# eeZeePowerJack.net
KiCad netlist of a schematic drawn in EAGLE
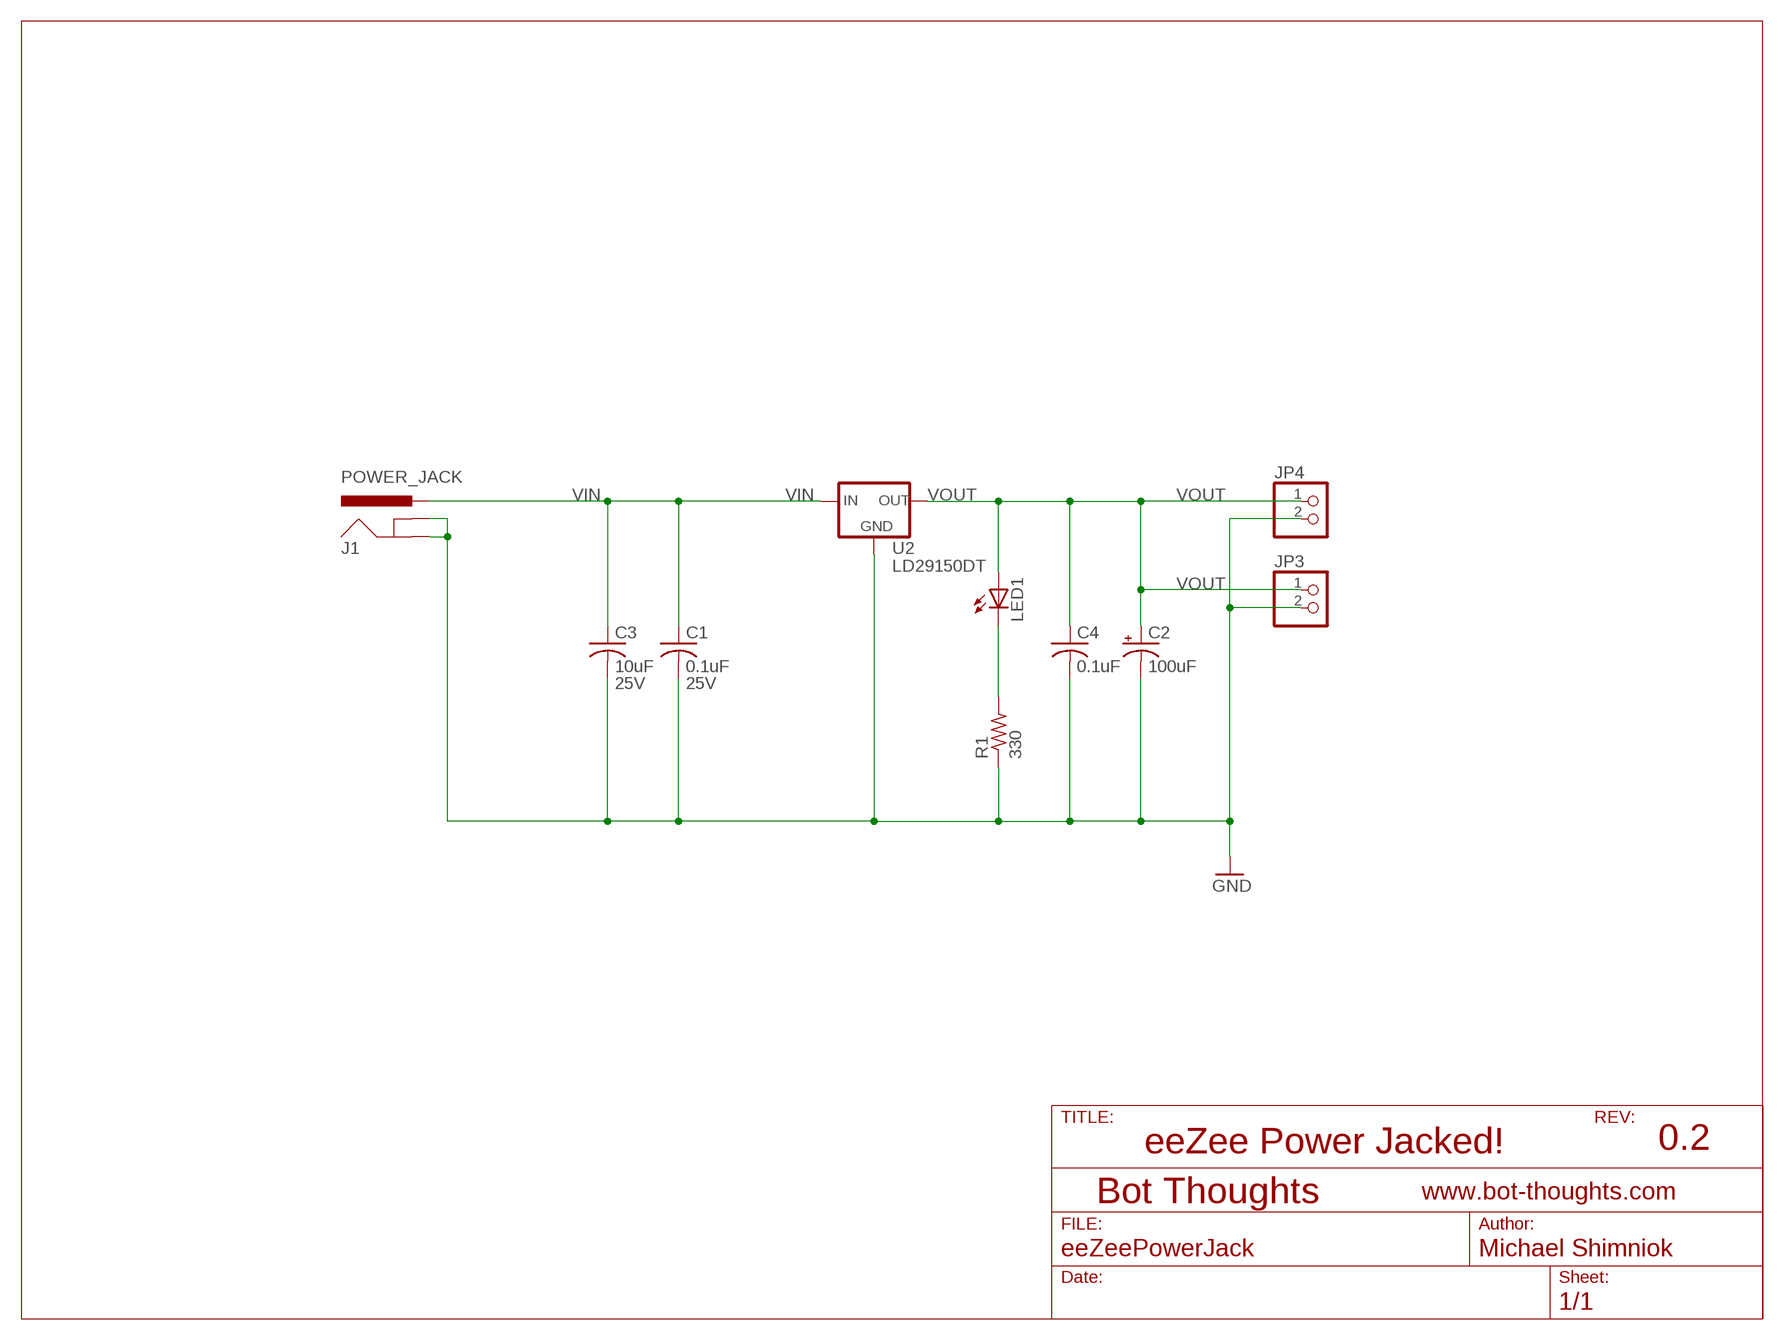
[diagram p0: schematic, sheet 1]

(export (version "E")
  (design (tool "Eeschema 10.0.6"))
  (components
    (comp (ref "C1")
      (value "0.1uF")
      (footprint "eagle-import:C0603")
      (fields (field (name "VOLTAGE") "25V"))
      (libsource (lib "eagle-import") (part "C-USC0603"))
    )
    (comp (ref "C2")
      (value "100uF")
      (footprint "eagle-import:SMC_B")
      (libsource (lib "eagle-import") (part "CPOL-USSMCB"))
    )
    (comp (ref "C3")
      (value "10uF")
      (footprint "eagle-import:C1206")
      (fields (field (name "VOLTAGE") "25V"))
      (libsource (lib "eagle-import") (part "C-USC1206"))
    )
    (comp (ref "C4")
      (value "0.1uF")
      (footprint "eagle-import:C0603")
      (libsource (lib "eagle-import") (part "C-USC0603"))
    )
    (comp (ref "J1")
      (value "POWER_JACK")
      (footprint "eagle-import:POWER_JACK_PTH")
      (libsource (lib "eagle-import") (part "POWER_JACKPTH"))
    )
    (comp (ref "JP3")
      (value "PINHD-1X02_2.54-S")
      (footprint "eagle-import:1X02-S")
      (libsource (lib "eagle-import") (part "PINHD-1X02_2.54-S"))
    )
    (comp (ref "JP4")
      (value "PINHD-1X02_2.54-S")
      (footprint "eagle-import:1X02-S")
      (libsource (lib "eagle-import") (part "PINHD-1X02_2.54-S"))
    )
    (comp (ref "LED1")
      (value "LEDCHIPLED_1206")
      (footprint "eagle-import:CHIPLED_1206")
      (libsource (lib "eagle-import") (part "LEDCHIPLED_1206"))
    )
    (comp (ref "R1")
      (value "330")
      (footprint "eagle-import:R0603")
      (libsource (lib "eagle-import") (part "R-US_R0603"))
    )
    (comp (ref "U2")
      (value "LD29150DT")
      (footprint "eagle-import:DPAK")
      (libsource (lib "eagle-import") (part "LD29150DT"))
    )
  )
  (nets
    (net (code "1") (name "/VIN") (class "Default")
      (node (ref "C1") (pin "1") (pinfunction "1_1") (pintype "passive"))
      (node (ref "C3") (pin "1") (pinfunction "1_1") (pintype "passive"))
      (node (ref "J1") (pin "PWR") (pinfunction "PWR_PWR") (pintype "bidirectional"))
      (node (ref "U2") (pin "1") (pinfunction "VIN_1") (pintype "bidirectional"))
    )
    (net (code "2") (name "/VOUT") (class "Default")
      (node (ref "C2") (pin "+") (pinfunction "+_+") (pintype "passive"))
      (node (ref "C4") (pin "1") (pinfunction "1_1") (pintype "passive"))
      (node (ref "JP3") (pin "1") (pinfunction "1_1") (pintype "passive"))
      (node (ref "JP4") (pin "1") (pinfunction "1_1") (pintype "passive"))
      (node (ref "LED1") (pin "A") (pinfunction "A_A") (pintype "passive"))
      (node (ref "U2") (pin "3") (pinfunction "VOUT_3") (pintype "bidirectional"))
    )
    (net (code "3") (name "GND") (class "Default")
      (node (ref "C1") (pin "2") (pinfunction "2_2") (pintype "passive"))
      (node (ref "C2") (pin "-") (pinfunction "-_-") (pintype "passive"))
      (node (ref "C3") (pin "2") (pinfunction "2_2") (pintype "passive"))
      (node (ref "C4") (pin "2") (pinfunction "2_2") (pintype "passive"))
      (node (ref "J1") (pin "GND") (pinfunction "GND_GND") (pintype "bidirectional"))
      (node (ref "J1") (pin "GNDBREAK") (pinfunction "GNDBREAK_GNDBREAK") (pintype "bidirectional"))
      (node (ref "JP3") (pin "2") (pinfunction "2_2") (pintype "passive"))
      (node (ref "JP4") (pin "2") (pinfunction "2_2") (pintype "passive"))
      (node (ref "R1") (pin "1") (pinfunction "1_1") (pintype "passive"))
      (node (ref "U2") (pin "4") (pinfunction "GND_4") (pintype "bidirectional"))
    )
    (net (code "4") (name "Net-(LED1-PadC)") (class "Default")
      (node (ref "LED1") (pin "C") (pinfunction "C_C") (pintype "passive"))
      (node (ref "R1") (pin "2") (pinfunction "2_2") (pintype "passive"))
    )
  )
)
